# PowerBoard.net
KiCad netlist of a schematic drawn in EAGLE
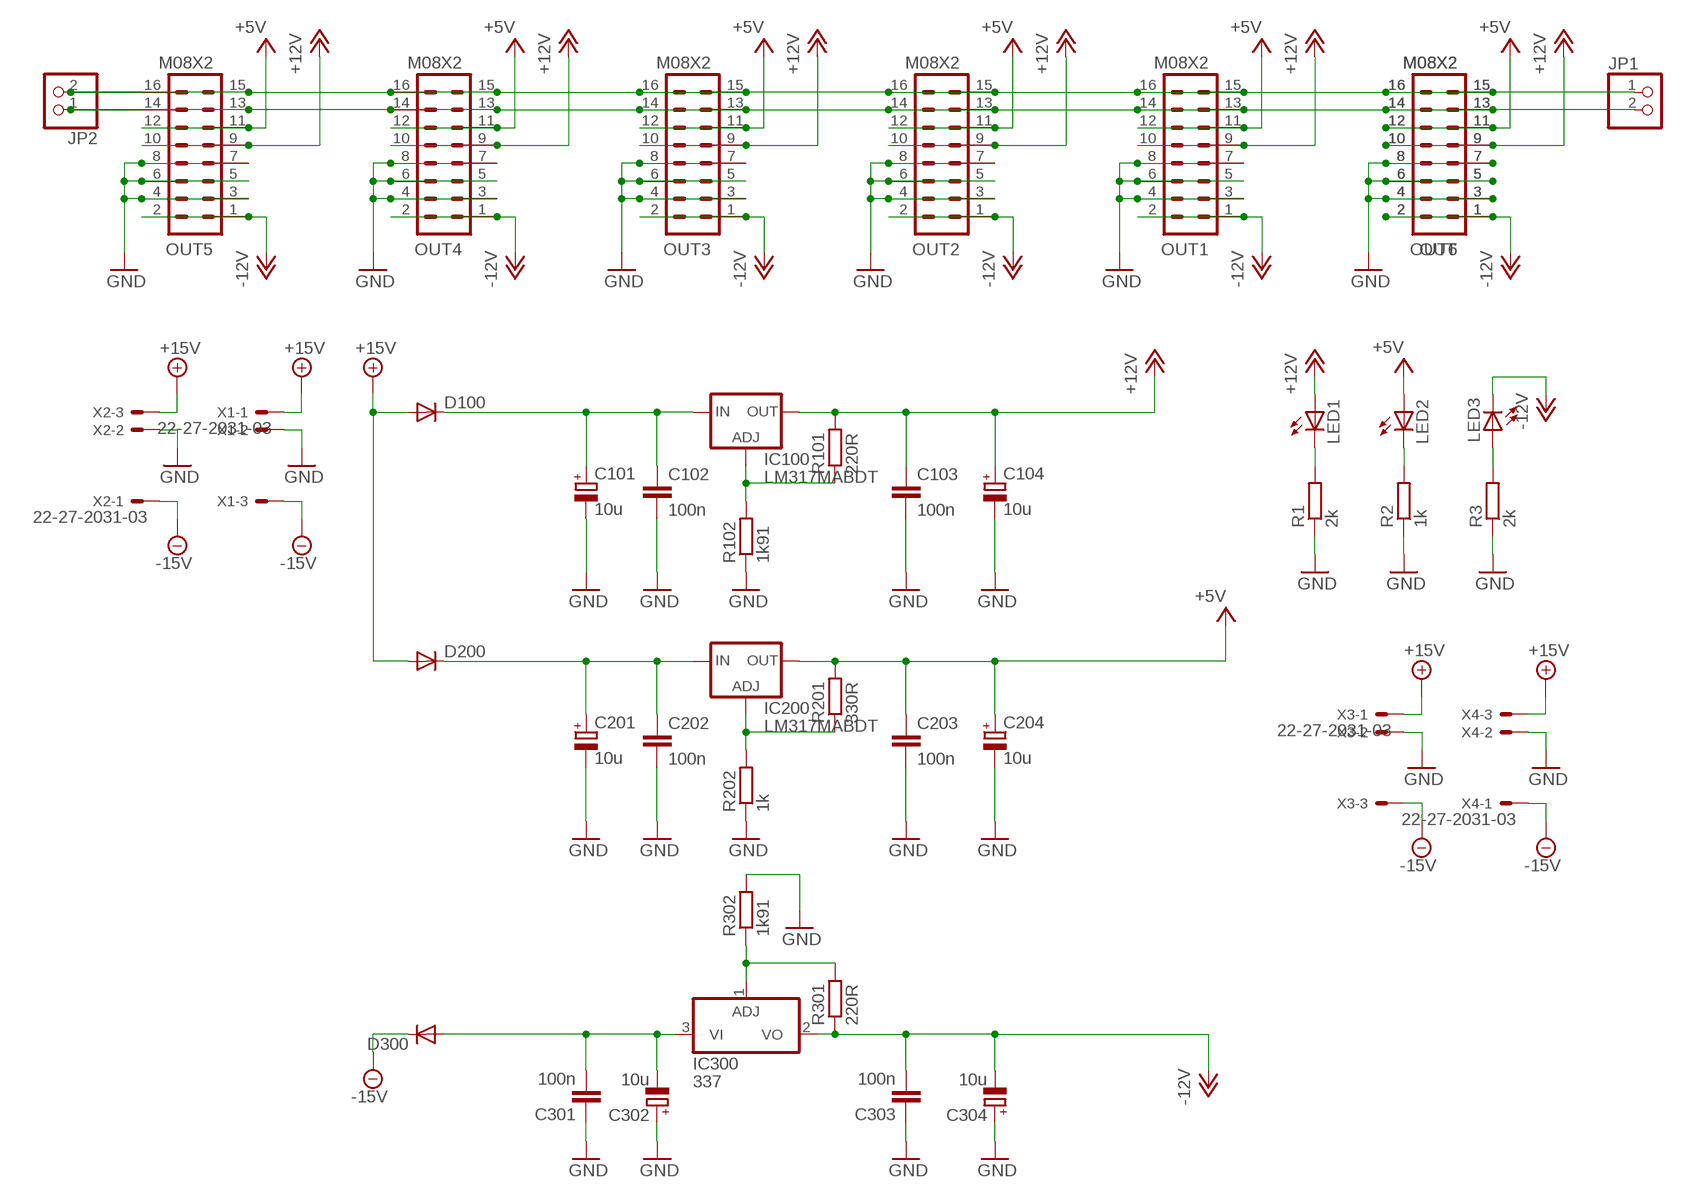
[diagram p0: schematic, sheet 1]

(export (version "E")
  (design (tool "Eeschema 10.0.6"))
  (components
    (comp (ref "C101")
      (value "10u")
      (footprint "eagle-import:153CLV-0810")
      (libsource (lib "eagle-import") (part "CPOL-EU153CLV-0810"))
    )
    (comp (ref "C102")
      (value "100n")
      (footprint "eagle-import:C0603")
      (libsource (lib "eagle-import") (part "C-EUC0603"))
    )
    (comp (ref "C103")
      (value "100n")
      (footprint "eagle-import:C0603")
      (libsource (lib "eagle-import") (part "C-EUC0603"))
    )
    (comp (ref "C104")
      (value "10u")
      (footprint "eagle-import:153CLV-0810")
      (libsource (lib "eagle-import") (part "CPOL-EU153CLV-0810"))
    )
    (comp (ref "C201")
      (value "10u")
      (footprint "eagle-import:153CLV-0810")
      (libsource (lib "eagle-import") (part "CPOL-EU153CLV-0810"))
    )
    (comp (ref "C202")
      (value "100n")
      (footprint "eagle-import:C0603")
      (libsource (lib "eagle-import") (part "C-EUC0603"))
    )
    (comp (ref "C203")
      (value "100n")
      (footprint "eagle-import:C0603")
      (libsource (lib "eagle-import") (part "C-EUC0603"))
    )
    (comp (ref "C204")
      (value "10u")
      (footprint "eagle-import:153CLV-0810")
      (libsource (lib "eagle-import") (part "CPOL-EU153CLV-0810"))
    )
    (comp (ref "C301")
      (value "100n")
      (footprint "eagle-import:C0603")
      (libsource (lib "eagle-import") (part "C-EUC0603"))
    )
    (comp (ref "C302")
      (value "10u")
      (footprint "eagle-import:153CLV-0810")
      (libsource (lib "eagle-import") (part "CPOL-EU153CLV-0810"))
    )
    (comp (ref "C303")
      (value "100n")
      (footprint "eagle-import:C0603")
      (libsource (lib "eagle-import") (part "C-EUC0603"))
    )
    (comp (ref "C304")
      (value "10u")
      (footprint "eagle-import:153CLV-0810")
      (libsource (lib "eagle-import") (part "CPOL-EU153CLV-0810"))
    )
    (comp (ref "D100")
      (value "DIODESMA")
      (footprint "eagle-import:SMA-DIODE")
      (libsource (lib "eagle-import") (part "DIODESMA"))
    )
    (comp (ref "D200")
      (value "DIODESMA")
      (footprint "eagle-import:SMA-DIODE")
      (libsource (lib "eagle-import") (part "DIODESMA"))
    )
    (comp (ref "D300")
      (value "DIODESMA")
      (footprint "eagle-import:SMA-DIODE")
      (libsource (lib "eagle-import") (part "DIODESMA"))
    )
    (comp (ref "IC100")
      (value "LM317MABDT")
      (footprint "eagle-import:DPACK")
      (libsource (lib "eagle-import") (part "v-reg_409_LM317?MABDT"))
    )
    (comp (ref "IC200")
      (value "LM317MABDT")
      (footprint "eagle-import:DPACK")
      (libsource (lib "eagle-import") (part "v-reg_409_LM317?MABDT"))
    )
    (comp (ref "IC300")
      (value "337")
      (footprint "eagle-import:TO252")
      (libsource (lib "eagle-import") (part "337"))
    )
    (comp (ref "JP1")
      (value "PINHD-1X2")
      (footprint "eagle-import:1X02")
      (libsource (lib "eagle-import") (part "PINHD-1X2"))
    )
    (comp (ref "JP2")
      (value "PINHD-1X2")
      (footprint "eagle-import:1X02")
      (libsource (lib "eagle-import") (part "PINHD-1X2"))
    )
    (comp (ref "LED1")
      (value "LEDCHIPLED_1206")
      (footprint "eagle-import:CHIPLED_1206")
      (libsource (lib "eagle-import") (part "LEDCHIPLED_1206"))
    )
    (comp (ref "LED2")
      (value "LEDCHIPLED_1206")
      (footprint "eagle-import:CHIPLED_1206")
      (libsource (lib "eagle-import") (part "LEDCHIPLED_1206"))
    )
    (comp (ref "LED3")
      (value "LEDCHIPLED_1206")
      (footprint "eagle-import:CHIPLED_1206")
      (libsource (lib "eagle-import") (part "LEDCHIPLED_1206"))
    )
    (comp (ref "OUT")
      (value "M08X2")
      (footprint "eagle-import:2X8")
      (libsource (lib "eagle-import") (part "M08X2"))
    )
    (comp (ref "OUT1")
      (value "M08X2")
      (footprint "eagle-import:2X8")
      (libsource (lib "eagle-import") (part "M08X2"))
    )
    (comp (ref "OUT2")
      (value "M08X2")
      (footprint "eagle-import:2X8")
      (libsource (lib "eagle-import") (part "M08X2"))
    )
    (comp (ref "OUT3")
      (value "M08X2")
      (footprint "eagle-import:2X8")
      (libsource (lib "eagle-import") (part "M08X2"))
    )
    (comp (ref "OUT4")
      (value "M08X2")
      (footprint "eagle-import:2X8")
      (libsource (lib "eagle-import") (part "M08X2"))
    )
    (comp (ref "OUT5")
      (value "M08X2")
      (footprint "eagle-import:2X8")
      (libsource (lib "eagle-import") (part "M08X2"))
    )
    (comp (ref "OUT6")
      (value "M08X2")
      (footprint "eagle-import:2X8")
      (libsource (lib "eagle-import") (part "M08X2"))
    )
    (comp (ref "R1")
      (value "2k")
      (footprint "eagle-import:0603")
      (libsource (lib "eagle-import") (part "R-EU_0603"))
    )
    (comp (ref "R2")
      (value "1k")
      (footprint "eagle-import:0603")
      (libsource (lib "eagle-import") (part "R-EU_0603"))
    )
    (comp (ref "R3")
      (value "2k")
      (footprint "eagle-import:0603")
      (libsource (lib "eagle-import") (part "R-EU_0603"))
    )
    (comp (ref "R101")
      (value "220R")
      (footprint "eagle-import:0603")
      (libsource (lib "eagle-import") (part "R-EU_0603"))
    )
    (comp (ref "R102")
      (value "1k91")
      (footprint "eagle-import:0603")
      (libsource (lib "eagle-import") (part "R-EU_0603"))
    )
    (comp (ref "R201")
      (value "330R")
      (footprint "eagle-import:0603")
      (libsource (lib "eagle-import") (part "R-EU_0603"))
    )
    (comp (ref "R202")
      (value "1k")
      (footprint "eagle-import:0603")
      (libsource (lib "eagle-import") (part "R-EU_0603"))
    )
    (comp (ref "R301")
      (value "220R")
      (footprint "eagle-import:0603")
      (libsource (lib "eagle-import") (part "R-EU_0603"))
    )
    (comp (ref "R302")
      (value "1k91")
      (footprint "eagle-import:0603")
      (libsource (lib "eagle-import") (part "R-EU_0603"))
    )
    (comp (ref "X1")
      (value "22-27-2031-03")
      (footprint "eagle-import:6410-03")
      (fields (field (name "MF") "MOLEX"))
      (libsource (lib "eagle-import") (part "22-?-0327-2031"))
    )
    (comp (ref "X2")
      (value "22-27-2031-03")
      (footprint "eagle-import:6410-03")
      (fields (field (name "MF") "MOLEX"))
      (libsource (lib "eagle-import") (part "22-?-0327-2031"))
    )
    (comp (ref "X3")
      (value "22-27-2031-03")
      (footprint "eagle-import:6410-03")
      (fields (field (name "MF") "MOLEX"))
      (libsource (lib "eagle-import") (part "22-?-0327-2031"))
    )
    (comp (ref "X4")
      (value "22-27-2031-03")
      (footprint "eagle-import:6410-03")
      (fields (field (name "MF") "MOLEX"))
      (libsource (lib "eagle-import") (part "22-?-0327-2031"))
    )
  )
  (nets
    (net (code "1") (name "+5V") (class "Default")
      (node (ref "C203") (pin "1") (pinfunction "1_1") (pintype "passive"))
      (node (ref "C204") (pin "+") (pinfunction "+_+") (pintype "passive"))
      (node (ref "IC200") (pin "4") (pinfunction "OUT_4") (pintype "passive"))
      (node (ref "LED2") (pin "A") (pinfunction "A_A") (pintype "passive"))
      (node (ref "OUT") (pin "11") (pinfunction "11_11") (pintype "passive"))
      (node (ref "OUT") (pin "12") (pinfunction "12_12") (pintype "passive"))
      (node (ref "OUT1") (pin "11") (pinfunction "11_11") (pintype "passive"))
      (node (ref "OUT1") (pin "12") (pinfunction "12_12") (pintype "passive"))
      (node (ref "OUT2") (pin "11") (pinfunction "11_11") (pintype "passive"))
      (node (ref "OUT2") (pin "12") (pinfunction "12_12") (pintype "passive"))
      (node (ref "OUT3") (pin "11") (pinfunction "11_11") (pintype "passive"))
      (node (ref "OUT3") (pin "12") (pinfunction "12_12") (pintype "passive"))
      (node (ref "OUT4") (pin "11") (pinfunction "11_11") (pintype "passive"))
      (node (ref "OUT4") (pin "12") (pinfunction "12_12") (pintype "passive"))
      (node (ref "OUT5") (pin "11") (pinfunction "11_11") (pintype "passive"))
      (node (ref "OUT5") (pin "12") (pinfunction "12_12") (pintype "passive"))
      (node (ref "OUT6") (pin "11") (pinfunction "11_11") (pintype "passive"))
      (node (ref "OUT6") (pin "12") (pinfunction "12_12") (pintype "passive"))
      (node (ref "R201") (pin "2") (pinfunction "2_2") (pintype "passive"))
    )
    (net (code "2") (name "+12V") (class "Default")
      (node (ref "C103") (pin "1") (pinfunction "1_1") (pintype "passive"))
      (node (ref "C104") (pin "+") (pinfunction "+_+") (pintype "passive"))
      (node (ref "IC100") (pin "4") (pinfunction "OUT_4") (pintype "passive"))
      (node (ref "LED1") (pin "A") (pinfunction "A_A") (pintype "passive"))
      (node (ref "OUT") (pin "10") (pinfunction "10_10") (pintype "passive"))
      (node (ref "OUT") (pin "9") (pinfunction "9_9") (pintype "passive"))
      (node (ref "OUT1") (pin "10") (pinfunction "10_10") (pintype "passive"))
      (node (ref "OUT1") (pin "9") (pinfunction "9_9") (pintype "passive"))
      (node (ref "OUT2") (pin "10") (pinfunction "10_10") (pintype "passive"))
      (node (ref "OUT2") (pin "9") (pinfunction "9_9") (pintype "passive"))
      (node (ref "OUT3") (pin "10") (pinfunction "10_10") (pintype "passive"))
      (node (ref "OUT3") (pin "9") (pinfunction "9_9") (pintype "passive"))
      (node (ref "OUT4") (pin "10") (pinfunction "10_10") (pintype "passive"))
      (node (ref "OUT4") (pin "9") (pinfunction "9_9") (pintype "passive"))
      (node (ref "OUT5") (pin "10") (pinfunction "10_10") (pintype "passive"))
      (node (ref "OUT5") (pin "9") (pinfunction "9_9") (pintype "passive"))
      (node (ref "OUT6") (pin "10") (pinfunction "10_10") (pintype "passive"))
      (node (ref "OUT6") (pin "9") (pinfunction "9_9") (pintype "passive"))
      (node (ref "R101") (pin "2") (pinfunction "2_2") (pintype "passive"))
    )
    (net (code "3") (name "+15V") (class "Default")
      (node (ref "D100") (pin "A") (pinfunction "A_A") (pintype "passive"))
      (node (ref "D200") (pin "A") (pinfunction "A_A") (pintype "passive"))
      (node (ref "X1") (pin "1") (pinfunction "S_1") (pintype "passive"))
      (node (ref "X2") (pin "3") (pinfunction "S_3") (pintype "passive"))
      (node (ref "X3") (pin "1") (pinfunction "S_1") (pintype "passive"))
      (node (ref "X4") (pin "3") (pinfunction "S_3") (pintype "passive"))
    )
    (net (code "4") (name "-12V") (class "Default")
      (node (ref "C303") (pin "2") (pinfunction "2_2") (pintype "passive"))
      (node (ref "C304") (pin "-") (pinfunction "-_-") (pintype "passive"))
      (node (ref "IC300") (pin "2") (pinfunction "VO_2") (pintype "passive"))
      (node (ref "LED3") (pin "C") (pinfunction "C_C") (pintype "passive"))
      (node (ref "OUT") (pin "1") (pinfunction "1_1") (pintype "passive"))
      (node (ref "OUT") (pin "2") (pinfunction "2_2") (pintype "passive"))
      (node (ref "OUT1") (pin "1") (pinfunction "1_1") (pintype "passive"))
      (node (ref "OUT1") (pin "2") (pinfunction "2_2") (pintype "passive"))
      (node (ref "OUT2") (pin "1") (pinfunction "1_1") (pintype "passive"))
      (node (ref "OUT2") (pin "2") (pinfunction "2_2") (pintype "passive"))
      (node (ref "OUT3") (pin "1") (pinfunction "1_1") (pintype "passive"))
      (node (ref "OUT3") (pin "2") (pinfunction "2_2") (pintype "passive"))
      (node (ref "OUT4") (pin "1") (pinfunction "1_1") (pintype "passive"))
      (node (ref "OUT4") (pin "2") (pinfunction "2_2") (pintype "passive"))
      (node (ref "OUT5") (pin "1") (pinfunction "1_1") (pintype "passive"))
      (node (ref "OUT5") (pin "2") (pinfunction "2_2") (pintype "passive"))
      (node (ref "OUT6") (pin "1") (pinfunction "1_1") (pintype "passive"))
      (node (ref "OUT6") (pin "2") (pinfunction "2_2") (pintype "passive"))
      (node (ref "R301") (pin "1") (pinfunction "1_1") (pintype "passive"))
    )
    (net (code "5") (name "-15V") (class "Default")
      (node (ref "D300") (pin "C") (pinfunction "C_C") (pintype "passive"))
      (node (ref "X1") (pin "3") (pinfunction "S_3") (pintype "passive"))
      (node (ref "X2") (pin "1") (pinfunction "S_1") (pintype "passive"))
      (node (ref "X3") (pin "3") (pinfunction "S_3") (pintype "passive"))
      (node (ref "X4") (pin "1") (pinfunction "S_1") (pintype "passive"))
    )
    (net (code "6") (name "GND") (class "Default")
      (node (ref "C101") (pin "-") (pinfunction "-_-") (pintype "passive"))
      (node (ref "C102") (pin "2") (pinfunction "2_2") (pintype "passive"))
      (node (ref "C103") (pin "2") (pinfunction "2_2") (pintype "passive"))
      (node (ref "C104") (pin "-") (pinfunction "-_-") (pintype "passive"))
      (node (ref "C201") (pin "-") (pinfunction "-_-") (pintype "passive"))
      (node (ref "C202") (pin "2") (pinfunction "2_2") (pintype "passive"))
      (node (ref "C203") (pin "2") (pinfunction "2_2") (pintype "passive"))
      (node (ref "C204") (pin "-") (pinfunction "-_-") (pintype "passive"))
      (node (ref "C301") (pin "1") (pinfunction "1_1") (pintype "passive"))
      (node (ref "C302") (pin "+") (pinfunction "+_+") (pintype "passive"))
      (node (ref "C303") (pin "1") (pinfunction "1_1") (pintype "passive"))
      (node (ref "C304") (pin "+") (pinfunction "+_+") (pintype "passive"))
      (node (ref "OUT") (pin "3") (pinfunction "3_3") (pintype "passive"))
      (node (ref "OUT") (pin "4") (pinfunction "4_4") (pintype "passive"))
      (node (ref "OUT") (pin "5") (pinfunction "5_5") (pintype "passive"))
      (node (ref "OUT") (pin "6") (pinfunction "6_6") (pintype "passive"))
      (node (ref "OUT") (pin "7") (pinfunction "7_7") (pintype "passive"))
      (node (ref "OUT") (pin "8") (pinfunction "8_8") (pintype "passive"))
      (node (ref "OUT1") (pin "3") (pinfunction "3_3") (pintype "passive"))
      (node (ref "OUT1") (pin "4") (pinfunction "4_4") (pintype "passive"))
      (node (ref "OUT1") (pin "5") (pinfunction "5_5") (pintype "passive"))
      (node (ref "OUT1") (pin "6") (pinfunction "6_6") (pintype "passive"))
      (node (ref "OUT1") (pin "7") (pinfunction "7_7") (pintype "passive"))
      (node (ref "OUT1") (pin "8") (pinfunction "8_8") (pintype "passive"))
      (node (ref "OUT2") (pin "3") (pinfunction "3_3") (pintype "passive"))
      (node (ref "OUT2") (pin "4") (pinfunction "4_4") (pintype "passive"))
      (node (ref "OUT2") (pin "5") (pinfunction "5_5") (pintype "passive"))
      (node (ref "OUT2") (pin "6") (pinfunction "6_6") (pintype "passive"))
      (node (ref "OUT2") (pin "7") (pinfunction "7_7") (pintype "passive"))
      (node (ref "OUT2") (pin "8") (pinfunction "8_8") (pintype "passive"))
      (node (ref "OUT3") (pin "3") (pinfunction "3_3") (pintype "passive"))
      (node (ref "OUT3") (pin "4") (pinfunction "4_4") (pintype "passive"))
      (node (ref "OUT3") (pin "5") (pinfunction "5_5") (pintype "passive"))
      (node (ref "OUT3") (pin "6") (pinfunction "6_6") (pintype "passive"))
      (node (ref "OUT3") (pin "7") (pinfunction "7_7") (pintype "passive"))
      (node (ref "OUT3") (pin "8") (pinfunction "8_8") (pintype "passive"))
      (node (ref "OUT4") (pin "3") (pinfunction "3_3") (pintype "passive"))
      (node (ref "OUT4") (pin "4") (pinfunction "4_4") (pintype "passive"))
      (node (ref "OUT4") (pin "5") (pinfunction "5_5") (pintype "passive"))
      (node (ref "OUT4") (pin "6") (pinfunction "6_6") (pintype "passive"))
      (node (ref "OUT4") (pin "7") (pinfunction "7_7") (pintype "passive"))
      (node (ref "OUT4") (pin "8") (pinfunction "8_8") (pintype "passive"))
      (node (ref "OUT5") (pin "3") (pinfunction "3_3") (pintype "passive"))
      (node (ref "OUT5") (pin "4") (pinfunction "4_4") (pintype "passive"))
      (node (ref "OUT5") (pin "5") (pinfunction "5_5") (pintype "passive"))
      (node (ref "OUT5") (pin "6") (pinfunction "6_6") (pintype "passive"))
      (node (ref "OUT5") (pin "7") (pinfunction "7_7") (pintype "passive"))
      (node (ref "OUT5") (pin "8") (pinfunction "8_8") (pintype "passive"))
      (node (ref "OUT6") (pin "3") (pinfunction "3_3") (pintype "passive"))
      (node (ref "OUT6") (pin "4") (pinfunction "4_4") (pintype "passive"))
      (node (ref "OUT6") (pin "5") (pinfunction "5_5") (pintype "passive"))
      (node (ref "OUT6") (pin "6") (pinfunction "6_6") (pintype "passive"))
      (node (ref "OUT6") (pin "7") (pinfunction "7_7") (pintype "passive"))
      (node (ref "OUT6") (pin "8") (pinfunction "8_8") (pintype "passive"))
      (node (ref "R1") (pin "1") (pinfunction "1_1") (pintype "passive"))
      (node (ref "R102") (pin "1") (pinfunction "1_1") (pintype "passive"))
      (node (ref "R2") (pin "1") (pinfunction "1_1") (pintype "passive"))
      (node (ref "R202") (pin "1") (pinfunction "1_1") (pintype "passive"))
      (node (ref "R3") (pin "1") (pinfunction "1_1") (pintype "passive"))
      (node (ref "R302") (pin "2") (pinfunction "2_2") (pintype "passive"))
      (node (ref "X1") (pin "2") (pinfunction "S_2") (pintype "passive"))
      (node (ref "X2") (pin "2") (pinfunction "S_2") (pintype "passive"))
      (node (ref "X3") (pin "2") (pinfunction "S_2") (pintype "passive"))
      (node (ref "X4") (pin "2") (pinfunction "S_2") (pintype "passive"))
    )
    (net (code "7") (name "Net-(IC100-ADJ)") (class "Default")
      (node (ref "IC100") (pin "1") (pinfunction "ADJ_1") (pintype "input"))
      (node (ref "R101") (pin "1") (pinfunction "1_1") (pintype "passive"))
      (node (ref "R102") (pin "2") (pinfunction "2_2") (pintype "passive"))
    )
    (net (code "8") (name "Net-(IC100-IN)") (class "Default")
      (node (ref "C101") (pin "+") (pinfunction "+_+") (pintype "passive"))
      (node (ref "C102") (pin "1") (pinfunction "1_1") (pintype "passive"))
      (node (ref "D100") (pin "C") (pinfunction "C_C") (pintype "passive"))
      (node (ref "IC100") (pin "3") (pinfunction "IN_3") (pintype "input"))
    )
    (net (code "9") (name "Net-(IC200-ADJ)") (class "Default")
      (node (ref "IC200") (pin "1") (pinfunction "ADJ_1") (pintype "input"))
      (node (ref "R201") (pin "1") (pinfunction "1_1") (pintype "passive"))
      (node (ref "R202") (pin "2") (pinfunction "2_2") (pintype "passive"))
    )
    (net (code "10") (name "Net-(IC200-IN)") (class "Default")
      (node (ref "C201") (pin "+") (pinfunction "+_+") (pintype "passive"))
      (node (ref "C202") (pin "1") (pinfunction "1_1") (pintype "passive"))
      (node (ref "D200") (pin "C") (pinfunction "C_C") (pintype "passive"))
      (node (ref "IC200") (pin "3") (pinfunction "IN_3") (pintype "input"))
    )
    (net (code "11") (name "Net-(IC300-ADJ)") (class "Default")
      (node (ref "IC300") (pin "1") (pinfunction "ADJ_1") (pintype "input"))
      (node (ref "R301") (pin "2") (pinfunction "2_2") (pintype "passive"))
      (node (ref "R302") (pin "1") (pinfunction "1_1") (pintype "passive"))
    )
    (net (code "12") (name "Net-(IC300-VI)") (class "Default")
      (node (ref "C301") (pin "2") (pinfunction "2_2") (pintype "passive"))
      (node (ref "C302") (pin "-") (pinfunction "-_-") (pintype "passive"))
      (node (ref "D300") (pin "A") (pinfunction "A_A") (pintype "passive"))
      (node (ref "IC300") (pin "3") (pinfunction "VI_3") (pintype "input"))
    )
    (net (code "13") (name "Net-(JP1-Pad1)") (class "Default")
      (node (ref "JP1") (pin "1") (pinfunction "1_1") (pintype "passive"))
      (node (ref "JP2") (pin "2") (pinfunction "2_2") (pintype "passive"))
      (node (ref "OUT") (pin "15") (pinfunction "15_15") (pintype "passive"))
      (node (ref "OUT") (pin "16") (pinfunction "16_16") (pintype "passive"))
      (node (ref "OUT1") (pin "15") (pinfunction "15_15") (pintype "passive"))
      (node (ref "OUT1") (pin "16") (pinfunction "16_16") (pintype "passive"))
      (node (ref "OUT2") (pin "15") (pinfunction "15_15") (pintype "passive"))
      (node (ref "OUT2") (pin "16") (pinfunction "16_16") (pintype "passive"))
      (node (ref "OUT3") (pin "15") (pinfunction "15_15") (pintype "passive"))
      (node (ref "OUT3") (pin "16") (pinfunction "16_16") (pintype "passive"))
      (node (ref "OUT4") (pin "15") (pinfunction "15_15") (pintype "passive"))
      (node (ref "OUT4") (pin "16") (pinfunction "16_16") (pintype "passive"))
      (node (ref "OUT5") (pin "15") (pinfunction "15_15") (pintype "passive"))
      (node (ref "OUT5") (pin "16") (pinfunction "16_16") (pintype "passive"))
      (node (ref "OUT6") (pin "15") (pinfunction "15_15") (pintype "passive"))
      (node (ref "OUT6") (pin "16") (pinfunction "16_16") (pintype "passive"))
    )
    (net (code "14") (name "Net-(JP1-Pad2)") (class "Default")
      (node (ref "JP1") (pin "2") (pinfunction "2_2") (pintype "passive"))
      (node (ref "JP2") (pin "1") (pinfunction "1_1") (pintype "passive"))
      (node (ref "OUT") (pin "13") (pinfunction "13_13") (pintype "passive"))
      (node (ref "OUT") (pin "14") (pinfunction "14_14") (pintype "passive"))
      (node (ref "OUT1") (pin "13") (pinfunction "13_13") (pintype "passive"))
      (node (ref "OUT1") (pin "14") (pinfunction "14_14") (pintype "passive"))
      (node (ref "OUT2") (pin "13") (pinfunction "13_13") (pintype "passive"))
      (node (ref "OUT2") (pin "14") (pinfunction "14_14") (pintype "passive"))
      (node (ref "OUT3") (pin "13") (pinfunction "13_13") (pintype "passive"))
      (node (ref "OUT3") (pin "14") (pinfunction "14_14") (pintype "passive"))
      (node (ref "OUT4") (pin "13") (pinfunction "13_13") (pintype "passive"))
      (node (ref "OUT4") (pin "14") (pinfunction "14_14") (pintype "passive"))
      (node (ref "OUT5") (pin "13") (pinfunction "13_13") (pintype "passive"))
      (node (ref "OUT5") (pin "14") (pinfunction "14_14") (pintype "passive"))
      (node (ref "OUT6") (pin "13") (pinfunction "13_13") (pintype "passive"))
      (node (ref "OUT6") (pin "14") (pinfunction "14_14") (pintype "passive"))
    )
    (net (code "15") (name "Net-(LED1-PadC)") (class "Default")
      (node (ref "LED1") (pin "C") (pinfunction "C_C") (pintype "passive"))
      (node (ref "R1") (pin "2") (pinfunction "2_2") (pintype "passive"))
    )
    (net (code "16") (name "Net-(LED2-PadC)") (class "Default")
      (node (ref "LED2") (pin "C") (pinfunction "C_C") (pintype "passive"))
      (node (ref "R2") (pin "2") (pinfunction "2_2") (pintype "passive"))
    )
    (net (code "17") (name "Net-(LED3-PadA)") (class "Default")
      (node (ref "LED3") (pin "A") (pinfunction "A_A") (pintype "passive"))
      (node (ref "R3") (pin "2") (pinfunction "2_2") (pintype "passive"))
    )
  )
)
